# APS2.net
KiCad netlist of a schematic drawn in EAGLE
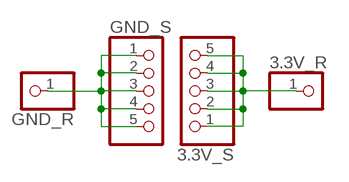
[diagram p0: schematic, sheet 1]

(export (version "E")
  (design (tool "Eeschema 10.0.6"))
  (components
    (comp (ref "3.3V_R")
      (value "PINHD-1X1")
      (footprint "eagle-import:1X01")
      (libsource (lib "eagle-import") (part "PINHD-1X1"))
    )
    (comp (ref "3.3V_S")
      (value "PINHD-1X5")
      (footprint "eagle-import:1X05")
      (libsource (lib "eagle-import") (part "PINHD-1X5"))
    )
    (comp (ref "GND_R")
      (value "PINHD-1X1")
      (footprint "eagle-import:1X01")
      (libsource (lib "eagle-import") (part "PINHD-1X1"))
    )
    (comp (ref "GND_S")
      (value "PINHD-1X5")
      (footprint "eagle-import:1X05")
      (libsource (lib "eagle-import") (part "PINHD-1X5"))
    )
  )
  (nets
    (net (code "1") (name "Net-(3.3V_R-Pad1)") (class "Default")
      (node (ref "3.3V_R") (pin "1") (pinfunction "1_1") (pintype "passive"))
      (node (ref "3.3V_S") (pin "1") (pinfunction "1_1") (pintype "passive"))
      (node (ref "3.3V_S") (pin "2") (pinfunction "2_2") (pintype "passive"))
      (node (ref "3.3V_S") (pin "3") (pinfunction "3_3") (pintype "passive"))
      (node (ref "3.3V_S") (pin "4") (pinfunction "4_4") (pintype "passive"))
      (node (ref "3.3V_S") (pin "5") (pinfunction "5_5") (pintype "passive"))
    )
    (net (code "2") (name "Net-(GND_R-Pad1)") (class "Default")
      (node (ref "GND_R") (pin "1") (pinfunction "1_1") (pintype "passive"))
      (node (ref "GND_S") (pin "1") (pinfunction "1_1") (pintype "passive"))
      (node (ref "GND_S") (pin "2") (pinfunction "2_2") (pintype "passive"))
      (node (ref "GND_S") (pin "3") (pinfunction "3_3") (pintype "passive"))
      (node (ref "GND_S") (pin "4") (pinfunction "4_4") (pintype "passive"))
      (node (ref "GND_S") (pin "5") (pinfunction "5_5") (pintype "passive"))
    )
  )
)
